# USB.net
KiCad netlist of a schematic drawn in EasyEDA Pro
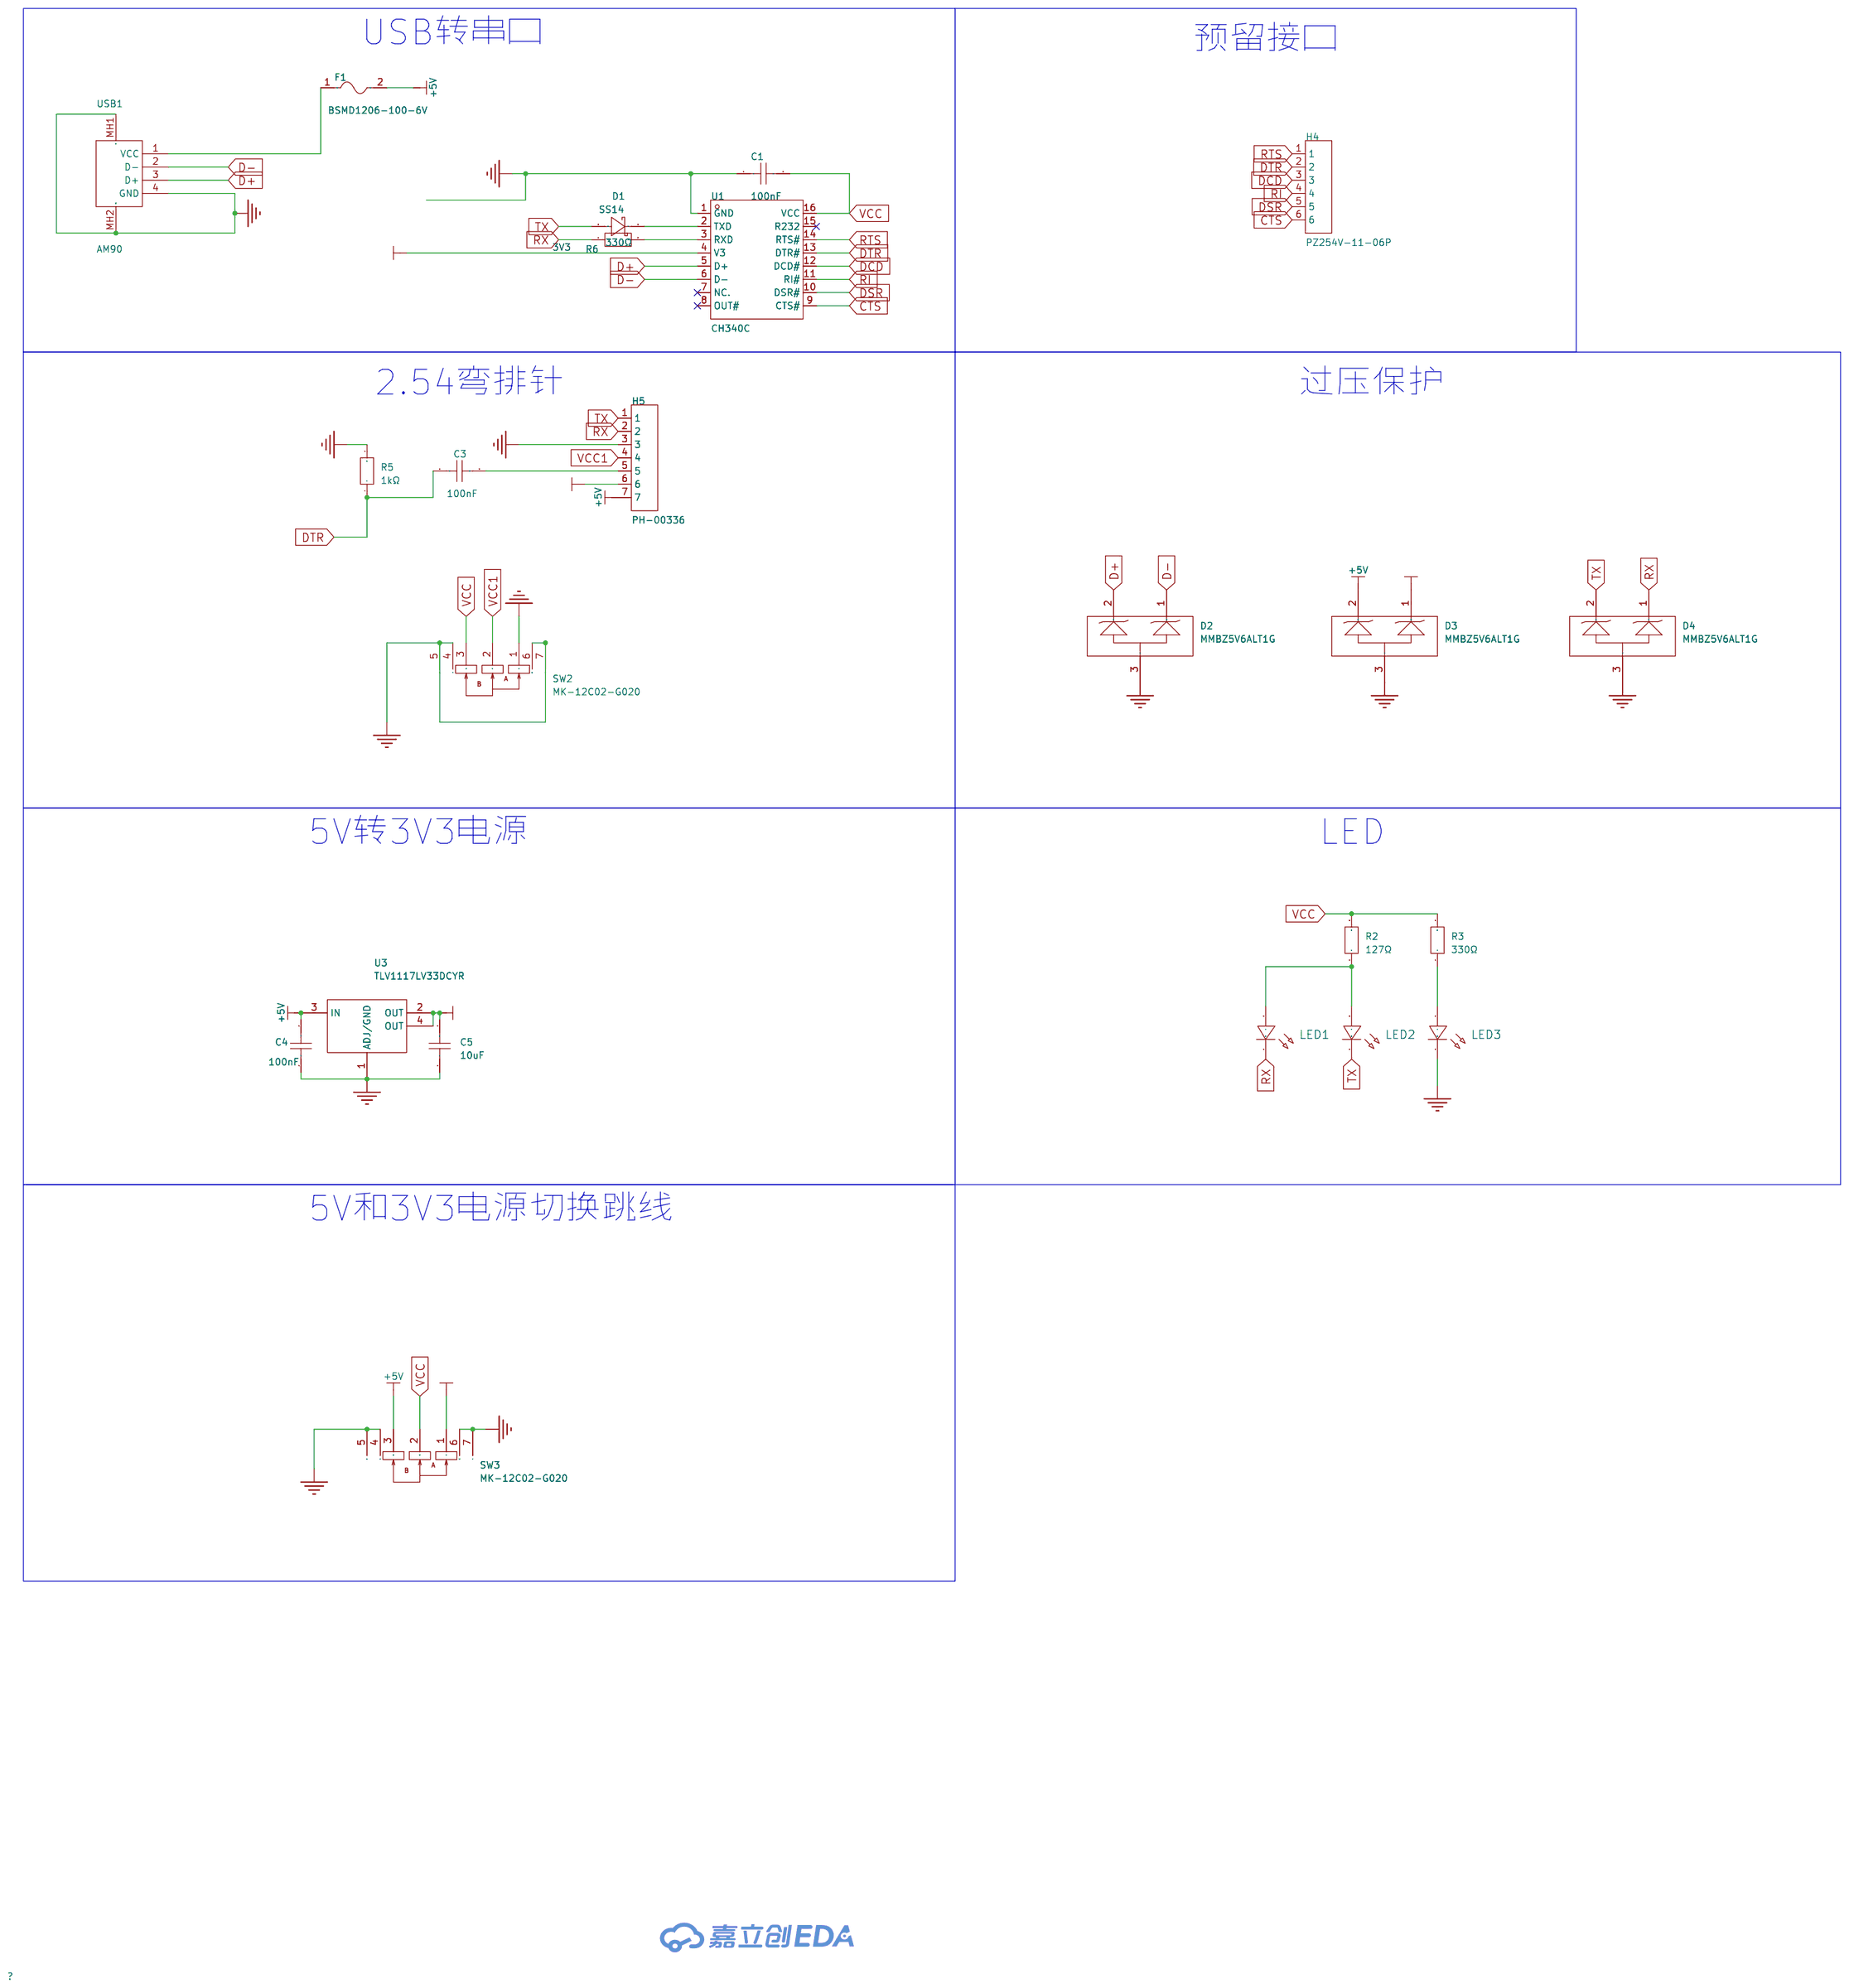
[diagram p0: schematic sheet]

(export (version "E")
  (design (tool "Eeschema 10.0.6"))
  (components
    (comp (ref "C1")
      (value "100nF")
      (footprint "easyedapro:C0805")
      (description "容值:100nF;精度:±10%;额定电压:50V;温度系数:X7R;")
      (fields (field (name "Manufacturer Part") "08055C104KAT4A") (field (name "Manufacturer") "Kyocera AVX"))
      (libsource (lib "easyedapro") (part "08055C104KAT4A"))
    )
    (comp (ref "C3")
      (value "100nF")
      (footprint "easyedapro:C0805")
      (description "容值:100nF;精度:±10%;额定电压:50V;温度系数:X7R;")
      (fields (field (name "Manufacturer Part") "08055C104KAT4A") (field (name "Manufacturer") "Kyocera AVX"))
      (libsource (lib "easyedapro") (part "08055C104KAT4A"))
    )
    (comp (ref "C4")
      (value "100nF")
      (footprint "easyedapro:C0805")
      (description "容值:100nF;精度:±10%;额定电压:50V;温度系数:X7R;")
      (fields (field (name "Manufacturer Part") "08055C104KAT4A") (field (name "Manufacturer") "Kyocera AVX"))
      (libsource (lib "easyedapro") (part "08055C104KAT4A"))
    )
    (comp (ref "C5")
      (value "10uF")
      (footprint "easyedapro:C0805")
      (description "容值:10uF;精度:±20%;额定电压:16V;温度系数:X6S;")
      (fields
        (field (name "Manufacturer Part") "CGA0805X6S106M160MT")
        (field (name "Manufacturer") "HRE(芯声)")
      )
      (libsource (lib "easyedapro") (part "CGA0805X6S106M160MT"))
    )
    (comp (ref "D1")
      (value "SS14")
      (footprint "easyedapro:SMA_L4.3-W2.6-LS5.0-RD")
      (description "二极管配置:独立式;正向压降(Vf):550mV@1A;直流反向耐压(Vr):40V;整流电流:1A;")
      (fields (field (name "Manufacturer") "TWGMC(台湾迪嘉)"))
      (libsource (lib "easyedapro") (part "SS14_C727050"))
    )
    (comp (ref "D2")
      (value "MMBZ5V6ALT1G")
      (footprint "easyedapro:SOT-23_L2.9-W1.3-P1.90-LS2.4-BR")
      (description "反向截止电压(Vrwm):3V;最大钳位电压:8V;峰值脉冲功率(Ppp)@10/1000us:24W;击穿电压:5.32V;")
      (fields (field (name "Manufacturer") "onsemi(安森美)"))
      (libsource (lib "easyedapro") (part "MMBZ5V6ALT1G"))
    )
    (comp (ref "D3")
      (value "MMBZ5V6ALT1G")
      (footprint "easyedapro:SOT-23_L2.9-W1.3-P1.90-LS2.4-BR")
      (description "反向截止电压(Vrwm):3V;最大钳位电压:8V;峰值脉冲功率(Ppp)@10/1000us:24W;击穿电压:5.32V;")
      (fields (field (name "Manufacturer") "onsemi(安森美)"))
      (libsource (lib "easyedapro") (part "MMBZ5V6ALT1G"))
    )
    (comp (ref "D4")
      (value "MMBZ5V6ALT1G")
      (footprint "easyedapro:SOT-23_L2.9-W1.3-P1.90-LS2.4-BR")
      (description "反向截止电压(Vrwm):3V;最大钳位电压:8V;峰值脉冲功率(Ppp)@10/1000us:24W;击穿电压:5.32V;")
      (fields (field (name "Manufacturer") "onsemi(安森美)"))
      (libsource (lib "easyedapro") (part "MMBZ5V6ALT1G"))
    )
    (comp (ref "F1")
      (value "BSMD1206-100-6V")
      (footprint "easyedapro:F1206")
      (description "耐压:6V;最大电流:100A;保持电流(Ih):1A;跳闸电流:1.8A;")
      (fields (field (name "Manufacturer") "BHFUSE(佰宏)"))
      (libsource (lib "easyedapro") (part "BSMD1206-100-6V"))
    )
    (comp (ref "H4")
      (value "PZ254V-11-06P")
      (footprint "easyedapro:HDR-TH_6P-P2.54-V-M")
      (fields (field (name "Manufacturer") "XFCN(兴飞)"))
      (libsource (lib "easyedapro") (part "PZ254V-11-06P"))
    )
    (comp (ref "H5")
      (value "PH-00336")
      (footprint "easyedapro:HDR-TH_7P-P2.54-V-M")
      (fields (field (name "Manufacturer") "Liansheng(连盛)"))
      (libsource (lib "easyedapro") (part "PH-00336"))
    )
    (comp (ref "LED1")
      (value "~")
      (footprint "easyedapro:LED_0603")
      (libsource (lib "easyedapro") (part "LED_R"))
    )
    (comp (ref "LED2")
      (value "~")
      (footprint "easyedapro:LED_0603")
      (libsource (lib "easyedapro") (part "LED_R"))
    )
    (comp (ref "LED3")
      (value "~")
      (footprint "easyedapro:LED_0603")
      (libsource (lib "easyedapro") (part "LED_R"))
    )
    (comp (ref "R2")
      (value "127Ω")
      (footprint "easyedapro:R0805")
      (description "电阻类型:厚膜电阻;阻值:127Ω;精度:±1%;功率:125mW;工作电压:150V;温度系数:±100ppm/°C;")
      (fields (field (name "Manufacturer Part") "FRC0805F1270TS") (field (name "Manufacturer") "FOJAN(富捷)"))
      (libsource (lib "easyedapro") (part "FRC0805F1270TS"))
    )
    (comp (ref "R3")
      (value "330Ω")
      (footprint "easyedapro:R0805")
      (description "电阻类型:厚膜电阻;阻值:330Ω;精度:±5%;功率:125mW;工作电压:-;温度系数:±200ppm/°C;")
      (fields
        (field (name "Manufacturer Part") "CRCW0805330RJNEA")
        (field (name "Manufacturer") "VISHAY(威世)")
      )
      (libsource (lib "easyedapro") (part "CRCW0805330RJNEA"))
    )
    (comp (ref "R5")
      (value "1kΩ")
      (footprint "easyedapro:R0805")
      (description "电阻类型:厚膜电阻;阻值:1kΩ;精度:±1%;功率:333mW;工作电压:150V;温度系数:±100ppm/°C;")
      (fields
        (field (name "Manufacturer Part") "HP05W3F1001T5E")
        (field (name "Manufacturer") "UNI-ROYAL(厚声)")
      )
      (libsource (lib "easyedapro") (part "HP05W3F1001T5E"))
    )
    (comp (ref "R6")
      (value "330Ω")
      (footprint "easyedapro:R0805")
      (description "电阻类型:厚膜电阻;阻值:330Ω;精度:±5%;功率:125mW;工作电压:-;温度系数:±200ppm/°C;")
      (fields
        (field (name "Manufacturer Part") "CRCW0805330RJNEA")
        (field (name "Manufacturer") "VISHAY(威世)")
      )
      (libsource (lib "easyedapro") (part "CRCW0805330RJNEA"))
    )
    (comp (ref "SW2")
      (value "MK-12C02-G020")
      (footprint "easyedapro:SW-SMD_MK-12C02-G020")
      (description "电路结构:单刀双掷;安装方式:卧贴;开关颜色:黑色;额定电流(DC):1A;额定电压(DC):6V;机械寿命:1万次;")
      (fields (field (name "Manufacturer") "G-Switch(品赞)"))
      (libsource (lib "easyedapro") (part "MK-12C02-G020"))
    )
    (comp (ref "SW3")
      (value "MK-12C02-G020")
      (footprint "easyedapro:SW-SMD_MK-12C02-G020")
      (description "电路结构:单刀双掷;安装方式:卧贴;开关颜色:黑色;额定电流(DC):1A;额定电压(DC):6V;机械寿命:1万次;")
      (fields (field (name "Manufacturer") "G-Switch(品赞)"))
      (libsource (lib "easyedapro") (part "MK-12C02-G020"))
    )
    (comp (ref "U1")
      (value "CH340C")
      (footprint "easyedapro:SOP-16_L10.0-W3.9-P1.27-LS6.0-BL")
      (description "应用功能:收发器;接口协议:USB 2.0;数据速率:2Mbps;")
      (fields (field (name "Manufacturer") "WCH(南京沁恒)"))
      (libsource (lib "easyedapro") (part "CH340C"))
    )
    (comp (ref "U3")
      (value "TLV1117LV33DCYR")
      (footprint "easyedapro:SOT-223_L6.7-W3.5-P2.30-BR")
      (description "输出类型:固定;最大输入电压:5.5V;输出电压:3.3V;输出电流:1A;电源纹波抑制比(PSRR):75dB@(120Hz);输出极性:正极;")
      (fields (field (name "Manufacturer") "TI(德州仪器)"))
      (libsource (lib "easyedapro") (part "TLV1117LV33DCYR"))
    )
    (comp (ref "USB1")
      (value "AM90")
      (footprint "easyedapro:USB-AM-TH_AM90")
      (description "连接器类型:Type-A;标准:USB 2.0;公母:公;安装方式:弯插;触点数量:4P;端口数量:1;额定电流 - 电源:1.5A;工作温度范围:-25°C~+85°C;")
      (fields (field (name "Manufacturer") "SHOU HAN(首韩)"))
      (libsource (lib "easyedapro") (part "AM90"))
    )
  )
  (nets
    (net (code "1") (name "+5V") (class "Default")
      (node (ref "C4") (pin "2") (pinfunction "2_2") (pintype "unspecified"))
      (node (ref "D3") (pin "2") (pinfunction "C_2") (pintype "unspecified"))
      (node (ref "F1") (pin "2") (pinfunction "2_2") (pintype "unspecified"))
      (node (ref "H5") (pin "7") (pinfunction "7_7") (pintype "unspecified"))
      (node (ref "SW3") (pin "3") (pinfunction "3_3") (pintype "unspecified"))
      (node (ref "U3") (pin "3") (pinfunction "IN_3") (pintype "unspecified"))
    )
    (net (code "2") (name "3V3") (class "Default")
      (node (ref "C5") (pin "2") (pinfunction "2_2") (pintype "unspecified"))
      (node (ref "D3") (pin "1") (pinfunction "C_1") (pintype "unspecified"))
      (node (ref "H5") (pin "6") (pinfunction "6_6") (pintype "unspecified"))
      (node (ref "SW3") (pin "1") (pinfunction "1_1") (pintype "unspecified"))
      (node (ref "U1") (pin "4") (pinfunction "V3_4") (pintype "unspecified"))
      (node (ref "U3") (pin "2") (pinfunction "OUT_2") (pintype "unspecified"))
      (node (ref "U3") (pin "4") (pinfunction "OUT_4") (pintype "unspecified"))
    )
    (net (code "3") (name "CTS") (class "Default")
      (node (ref "H4") (pin "6") (pinfunction "6_6") (pintype "unspecified"))
      (node (ref "U1") (pin "9") (pinfunction "CTS#_9") (pintype "unspecified"))
    )
    (net (code "4") (name "D+") (class "Default")
      (node (ref "D2") (pin "2") (pinfunction "C_2") (pintype "unspecified"))
      (node (ref "U1") (pin "5") (pinfunction "D+_5") (pintype "unspecified"))
      (node (ref "USB1") (pin "3") (pinfunction "D+_3") (pintype "input"))
    )
    (net (code "5") (name "D-") (class "Default")
      (node (ref "D2") (pin "1") (pinfunction "C_1") (pintype "unspecified"))
      (node (ref "U1") (pin "6") (pinfunction "D-_6") (pintype "unspecified"))
      (node (ref "USB1") (pin "2") (pinfunction "D-_2") (pintype "input"))
    )
    (net (code "6") (name "DCD") (class "Default")
      (node (ref "H4") (pin "3") (pinfunction "3_3") (pintype "unspecified"))
      (node (ref "U1") (pin "12") (pinfunction "DCD#_12") (pintype "unspecified"))
    )
    (net (code "7") (name "DSR") (class "Default")
      (node (ref "H4") (pin "5") (pinfunction "5_5") (pintype "unspecified"))
      (node (ref "U1") (pin "10") (pinfunction "DSR#_10") (pintype "unspecified"))
    )
    (net (code "8") (name "DTR") (class "Default")
      (node (ref "C3") (pin "1") (pinfunction "1_1") (pintype "unspecified"))
      (node (ref "H4") (pin "2") (pinfunction "2_2") (pintype "unspecified"))
      (node (ref "R5") (pin "1") (pinfunction "1_1") (pintype "unspecified"))
      (node (ref "U1") (pin "13") (pinfunction "DTR#_13") (pintype "unspecified"))
    )
    (net (code "9") (name "GND") (class "Default")
      (node (ref "C1") (pin "1") (pinfunction "1_1") (pintype "unspecified"))
      (node (ref "C4") (pin "1") (pinfunction "1_1") (pintype "unspecified"))
      (node (ref "C5") (pin "1") (pinfunction "1_1") (pintype "unspecified"))
      (node (ref "D2") (pin "3") (pinfunction "A_3") (pintype "unspecified"))
      (node (ref "D3") (pin "3") (pinfunction "A_3") (pintype "unspecified"))
      (node (ref "D4") (pin "3") (pinfunction "A_3") (pintype "unspecified"))
      (node (ref "H5") (pin "3") (pinfunction "3_3") (pintype "unspecified"))
      (node (ref "LED3") (pin "1") (pinfunction "C_1") (pintype "input"))
      (node (ref "R5") (pin "2") (pinfunction "2_2") (pintype "unspecified"))
      (node (ref "SW2") (pin "1") (pinfunction "1_1") (pintype "unspecified"))
      (node (ref "SW2") (pin "4") (pinfunction "4_4") (pintype "unspecified"))
      (node (ref "SW2") (pin "5") (pinfunction "5_5") (pintype "unspecified"))
      (node (ref "SW2") (pin "6") (pinfunction "6_6") (pintype "unspecified"))
      (node (ref "SW2") (pin "7") (pinfunction "7_7") (pintype "unspecified"))
      (node (ref "SW3") (pin "4") (pinfunction "4_4") (pintype "unspecified"))
      (node (ref "SW3") (pin "5") (pinfunction "5_5") (pintype "unspecified"))
      (node (ref "SW3") (pin "6") (pinfunction "6_6") (pintype "unspecified"))
      (node (ref "SW3") (pin "7") (pinfunction "7_7") (pintype "unspecified"))
      (node (ref "U1") (pin "1") (pinfunction "GND_1") (pintype "unspecified"))
      (node (ref "U3") (pin "1") (pinfunction "ADJ/GND_1") (pintype "unspecified"))
      (node (ref "USB1") (pin "4") (pinfunction "GND_4") (pintype "input"))
      (node (ref "USB1") (pin "MH1") (pinfunction "MH1_MH1") (pintype "unspecified"))
      (node (ref "USB1") (pin "MH2") (pinfunction "MH2_MH2") (pintype "unspecified"))
    )
    (net (code "10") (name "Net-(C3-Pad2)") (class "Default")
      (node (ref "C3") (pin "2") (pinfunction "2_2") (pintype "unspecified"))
      (node (ref "H5") (pin "5") (pinfunction "5_5") (pintype "unspecified"))
    )
    (net (code "11") (name "Net-(D1-K)") (class "Default")
      (node (ref "D1") (pin "1") (pinfunction "K_1") (pintype "unspecified"))
      (node (ref "U1") (pin "2") (pinfunction "TXD_2") (pintype "unspecified"))
    )
    (net (code "12") (name "Net-(LED1-A)") (class "Default")
      (node (ref "LED1") (pin "2") (pinfunction "A_2") (pintype "input"))
      (node (ref "LED2") (pin "2") (pinfunction "A_2") (pintype "input"))
      (node (ref "R2") (pin "1") (pinfunction "1_1") (pintype "unspecified"))
    )
    (net (code "13") (name "Net-(LED3-A)") (class "Default")
      (node (ref "LED3") (pin "2") (pinfunction "A_2") (pintype "input"))
      (node (ref "R3") (pin "1") (pinfunction "1_1") (pintype "unspecified"))
    )
    (net (code "14") (name "Net-(U1-RXD)") (class "Default")
      (node (ref "R6") (pin "2") (pinfunction "2_2") (pintype "unspecified"))
      (node (ref "U1") (pin "3") (pinfunction "RXD_3") (pintype "unspecified"))
    )
    (net (code "15") (name "Net-(USB1-VCC)") (class "Default")
      (node (ref "F1") (pin "1") (pinfunction "1_1") (pintype "unspecified"))
      (node (ref "USB1") (pin "1") (pinfunction "VCC_1") (pintype "input"))
    )
    (net (code "16") (name "RI") (class "Default")
      (node (ref "H4") (pin "4") (pinfunction "4_4") (pintype "unspecified"))
      (node (ref "U1") (pin "11") (pinfunction "RI#_11") (pintype "unspecified"))
    )
    (net (code "17") (name "RTS") (class "Default")
      (node (ref "H4") (pin "1") (pinfunction "1_1") (pintype "unspecified"))
      (node (ref "U1") (pin "14") (pinfunction "RTS#_14") (pintype "unspecified"))
    )
    (net (code "18") (name "RX") (class "Default")
      (node (ref "D4") (pin "1") (pinfunction "C_1") (pintype "unspecified"))
      (node (ref "H5") (pin "2") (pinfunction "2_2") (pintype "unspecified"))
      (node (ref "LED1") (pin "1") (pinfunction "C_1") (pintype "input"))
      (node (ref "R6") (pin "1") (pinfunction "1_1") (pintype "unspecified"))
    )
    (net (code "19") (name "TX") (class "Default")
      (node (ref "D1") (pin "2") (pinfunction "A_2") (pintype "unspecified"))
      (node (ref "D4") (pin "2") (pinfunction "C_2") (pintype "unspecified"))
      (node (ref "H5") (pin "1") (pinfunction "1_1") (pintype "unspecified"))
      (node (ref "LED2") (pin "1") (pinfunction "C_1") (pintype "input"))
    )
    (net (code "20") (name "VCC") (class "Default")
      (node (ref "C1") (pin "2") (pinfunction "2_2") (pintype "unspecified"))
      (node (ref "R2") (pin "2") (pinfunction "2_2") (pintype "unspecified"))
      (node (ref "R3") (pin "2") (pinfunction "2_2") (pintype "unspecified"))
      (node (ref "SW2") (pin "3") (pinfunction "3_3") (pintype "unspecified"))
      (node (ref "SW3") (pin "2") (pinfunction "2_2") (pintype "unspecified"))
      (node (ref "U1") (pin "16") (pinfunction "VCC_16") (pintype "unspecified"))
    )
    (net (code "21") (name "VCC1") (class "Default")
      (node (ref "H5") (pin "4") (pinfunction "4_4") (pintype "unspecified"))
      (node (ref "SW2") (pin "2") (pinfunction "2_2") (pintype "unspecified"))
    )
    (net (code "22") (name "unconnected-(U1-NC.-Pad7)") (class "Default")
      (node (ref "U1") (pin "7") (pinfunction "NC._7") (pintype "unspecified+no_connect"))
    )
    (net (code "23") (name "unconnected-(U1-OUT#-Pad8)") (class "Default")
      (node (ref "U1") (pin "8") (pinfunction "OUT#_8") (pintype "unspecified+no_connect"))
    )
    (net (code "24") (name "unconnected-(U1-R232-Pad15)") (class "Default")
      (node (ref "U1") (pin "15") (pinfunction "R232_15") (pintype "unspecified+no_connect"))
    )
  )
)
